# Final_Embedded.net
KiCad netlist of a schematic drawn in Altium Designer
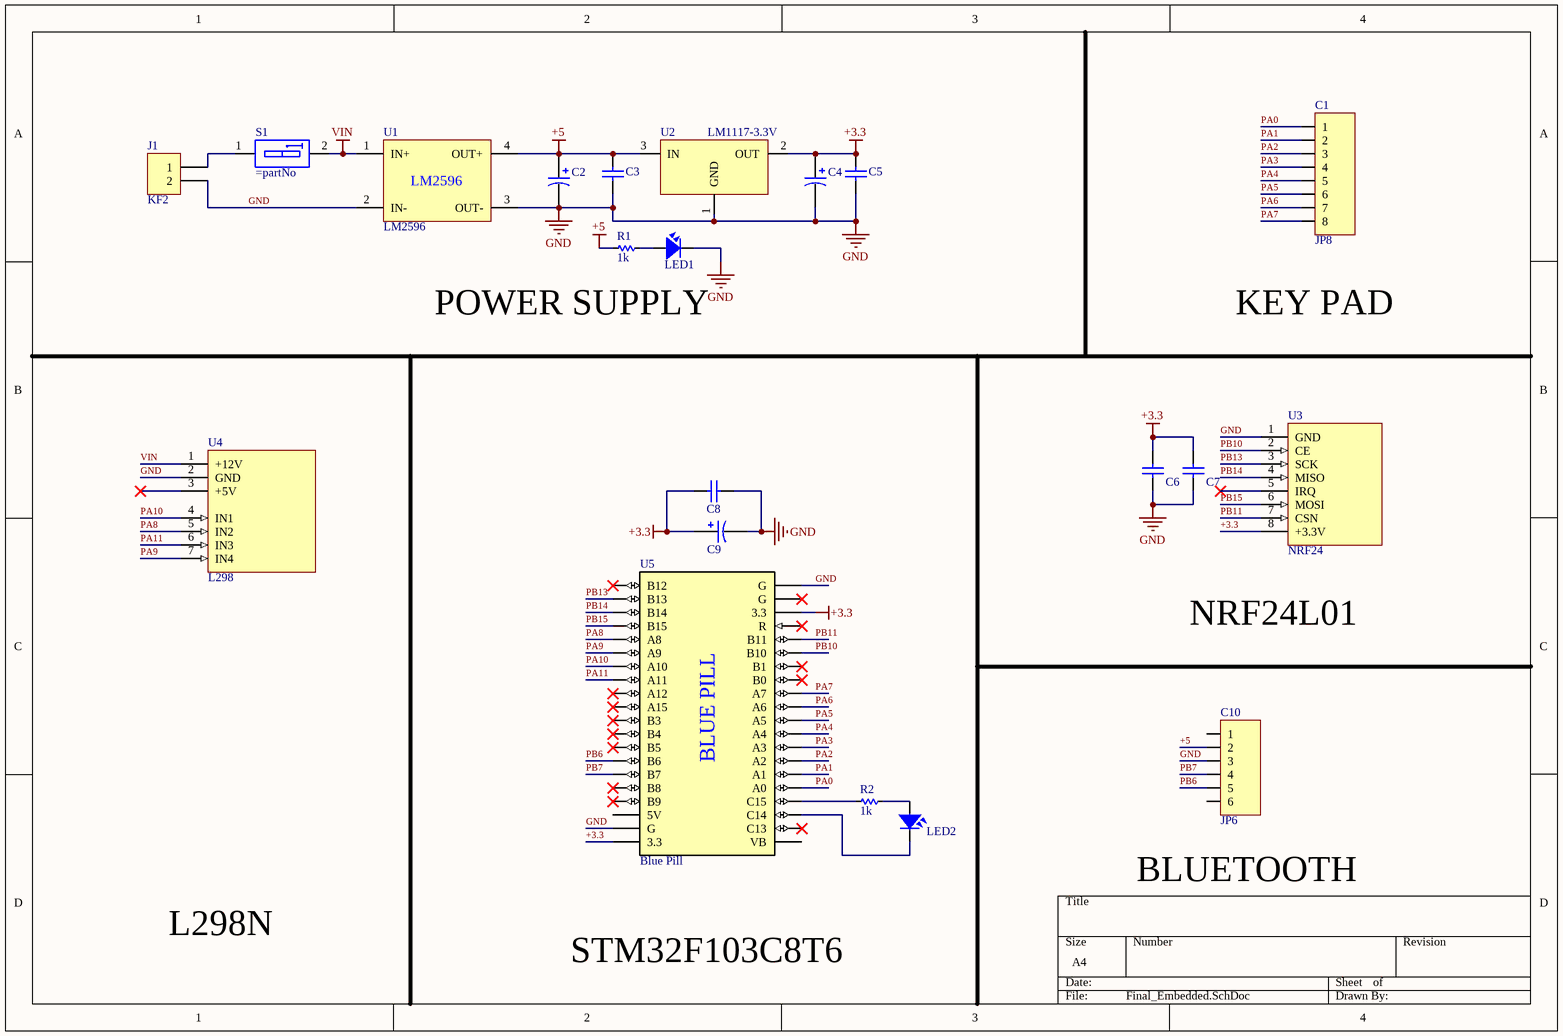
[diagram p0: Final_Embedded.SchDoc]

(export (version "E")
  (design (tool "Eeschema 10.0.6"))
  (components
    (comp (ref "C1")
      (value "JP8")
      (footprint "JP8-D1T")
      (description "WR-PHD 2.54 mm Angled Socket Header")
      (fields
        (field (name "MANUFACTURER") "Würth Elektronik eiSos GmbH")
        (field (name "PARTNO") "613008143121")
        (field (name "CREATED BY") "Karrer Zheng")
      )
      (libsource (lib "TechMT.VN_Lib_Project v2") (part "JP8"))
    )
    (comp (ref "C2")
      (value "47uF")
      (footprint "CAP_ALUM_D080_S35_H115")
      (description "CAP ALUM 47uF 20% 63V RADIAL")
      (fields (field (name "MPN") "CLA4512"))
      (libsource (lib "BYTECH_HW_LIB_2019 (1)") (part "CLA4512"))
    )
    (comp (ref "C3")
      (value "104")
      (footprint "Tu-pico")
      (description "Capacitor")
      (fields (field (name "PUBLISHER") "Altium Limited"))
      (libsource (lib "hphonglib") (part "CapCeramic"))
    )
    (comp (ref "C4")
      (value "47uF")
      (footprint "CAP_ALUM_D080_S35_H115")
      (description "CAP ALUM 47uF 20% 63V RADIAL")
      (fields (field (name "MPN") "CLA4512"))
      (libsource (lib "BYTECH_HW_LIB_2019 (1)") (part "CLA4512"))
    )
    (comp (ref "C5")
      (value "104")
      (footprint "Tu-pico")
      (description "Capacitor")
      (fields (field (name "PUBLISHER") "Altium Limited"))
      (libsource (lib "hphonglib") (part "CapCeramic"))
    )
    (comp (ref "C6")
      (value "104")
      (footprint "Tu-pico")
      (description "Capacitor")
      (fields (field (name "PUBLISHER") "Altium Limited"))
      (libsource (lib "hphonglib") (part "CapCeramic"))
    )
    (comp (ref "C7")
      (value "104")
      (footprint "Tu-pico")
      (description "Capacitor")
      (fields (field (name "PUBLISHER") "Altium Limited"))
      (libsource (lib "hphonglib") (part "CapCeramic"))
    )
    (comp (ref "C8")
      (value "104")
      (footprint "Tu-pico")
      (description "Capacitor")
      (fields (field (name "PUBLISHER") "Altium Limited"))
      (libsource (lib "hphonglib") (part "CapCeramic"))
    )
    (comp (ref "C9")
      (value "47uF")
      (footprint "CAP_ALUM_D080_S35_H115")
      (description "CAP ALUM 47uF 20% 63V RADIAL")
      (fields (field (name "MPN") "CLA4512"))
      (libsource (lib "BYTECH_HW_LIB_2019 (1)") (part "CLA4512"))
    )
    (comp (ref "C10")
      (value "JP6")
      (footprint "JP6-C1T")
      (description "WR-PHD 2.54 mm Angled Socket Header")
      (fields
        (field (name "MANUFACTURER") "Würth Elektronik eiSos GmbH")
        (field (name "PARTNO") "613006143121")
        (field (name "CREATED BY") "Karrer Zheng")
      )
      (libsource (lib "TechMT.VN_Lib_Project v2") (part "JP6"))
    )
    (comp (ref "J1")
      (value "KF2")
      (footprint "KF2-5.08")
      (fields
        (field (name "MANUFACTURER") "Würth Elektronik eiSos GmbH")
        (field (name "PARTNO") "691103110002")
        (field (name "CREATED BY") "Karrer Zheng")
      )
      (libsource (lib "TechMT.VN_Lib_Project v2") (part "KF2"))
    )
    (comp (ref "LED1")
      (value "LED")
      (footprint "LED-3MM-RED")
      (description "LED Single colour Green and Red")
      (libsource (lib "TechMT.VN_Lib_Project v2") (part "LED"))
    )
    (comp (ref "LED2")
      (value "LED")
      (footprint "LED-3MM-GREEN")
      (description "LED Single colour Green and Red")
      (libsource (lib "TechMT.VN_Lib_Project v2") (part "LED"))
    )
    (comp (ref "R1")
      (value "1k")
      (footprint "RES-1/4W-SMALL")
      (description "Res")
      (fields
        (field (name "MANUFACTURER") "Generic Components")
        (field (name "PUBLISHER") "Altium Hobart Technology Centre")
      )
      (libsource (lib "TechMT.VN_Lib_Project v2") (part "Res"))
    )
    (comp (ref "R2")
      (value "1k")
      (footprint "RES-1/8W-SMALL")
      (description "Res")
      (fields
        (field (name "MANUFACTURER") "Generic Components")
        (field (name "PUBLISHER") "Altium Hobart Technology Centre")
      )
      (libsource (lib "TechMT.VN_Lib_Project v2") (part "Res"))
    )
    (comp (ref "S1")
      (value "~")
      (footprint "SW-DIP1")
      (description "WS-DITV 2.54 mm small compact THT flat actuator with top tape")
      (fields
        (field (name "MANUFACTURER") "Wurth Elektronik")
        (field (name "PART NO.") "418127160901")
        (field (name "CREATED BY") "Baojun Chen")
      )
      (libsource (lib "LIBRARY") (part "SWDIP1"))
    )
    (comp (ref "U1")
      (value "LM2596")
      (footprint "AZ_Lib:LM2596 Module")
      (description "DC - DC Buck")
      (libsource (lib "AZ_Lib") (part "LM2596 Module"))
    )
    (comp (ref "U2")
      (value "LM1117-3.3V")
      (footprint "TO220-123")
      (description "800mA Low-Dropout Linear Regulator")
      (fields (field (name "CREATOR") "Nguyen Ba Bien"))
      (libsource (lib "TechMT.VN_Lib_Project v2") (part "LM1117"))
    )
    (comp (ref "U3")
      (value "NRF24")
      (footprint "AZ_Lib:NRF24L01 Module")
      (description "NRF24L01")
      (libsource (lib "AZ_Lib") (part "NRF24L01 Module"))
    )
    (comp (ref "U4")
      (value "L298")
      (footprint "AZ_Lib:L298N Module")
      (description "L298 Module")
      (libsource (lib "AZ_Lib") (part "L298N Module"))
    )
    (comp (ref "U5")
      (value "Blue Pill")
      (footprint "AZ_Lib:Blue Pill STM32F103")
      (description "Blue Pill STM32F103C8T6")
      (libsource (lib "AZ_Lib") (part "Blue Pill STM32F103"))
    )
  )
  (nets
    (net (code "1") (name "+3.3") (class "Default")
      (node (ref "C4") (pin "1") (pinfunction "1_1") (pintype "passive"))
      (node (ref "C5") (pin "2") (pinfunction "2_2") (pintype "passive"))
      (node (ref "C6") (pin "1") (pinfunction "1_1") (pintype "passive"))
      (node (ref "C7") (pin "1") (pinfunction "1_1") (pintype "passive"))
      (node (ref "C8") (pin "1") (pinfunction "1_1") (pintype "passive"))
      (node (ref "C9") (pin "1") (pinfunction "1_1") (pintype "passive"))
      (node (ref "U2") (pin "2") (pinfunction "OUT_2") (pintype "passive"))
      (node (ref "U3") (pin "8") (pinfunction "+3.3V_8") (pintype "power_in"))
      (node (ref "U5") (pin "20") (pinfunction "3.3_20") (pintype "power_in"))
      (node (ref "U5") (pin "38") (pinfunction "3.3_38") (pintype "power_in"))
    )
    (net (code "2") (name "+5") (class "Default")
      (node (ref "C10") (pin "2") (pinfunction "2_2") (pintype "passive"))
      (node (ref "C2") (pin "1") (pinfunction "1_1") (pintype "passive"))
      (node (ref "C3") (pin "2") (pinfunction "2_2") (pintype "passive"))
      (node (ref "R1") (pin "2") (pinfunction "2_2") (pintype "passive"))
      (node (ref "U1") (pin "4") (pinfunction "OUT+_4") (pintype "passive"))
      (node (ref "U2") (pin "3") (pinfunction "IN_3") (pintype "passive"))
    )
    (net (code "3") (name "/PA0") (class "Default")
      (node (ref "C1") (pin "1") (pinfunction "1_1") (pintype "passive"))
      (node (ref "U5") (pin "25") (pinfunction "A0_25") (pintype "bidirectional"))
    )
    (net (code "4") (name "/PA1") (class "Default")
      (node (ref "C1") (pin "2") (pinfunction "2_2") (pintype "passive"))
      (node (ref "U5") (pin "26") (pinfunction "A1_26") (pintype "bidirectional"))
    )
    (net (code "5") (name "/PA2") (class "Default")
      (node (ref "C1") (pin "3") (pinfunction "3_3") (pintype "passive"))
      (node (ref "U5") (pin "27") (pinfunction "A2_27") (pintype "bidirectional"))
    )
    (net (code "6") (name "/PA3") (class "Default")
      (node (ref "C1") (pin "4") (pinfunction "4_4") (pintype "passive"))
      (node (ref "U5") (pin "28") (pinfunction "A3_28") (pintype "bidirectional"))
    )
    (net (code "7") (name "/PA4") (class "Default")
      (node (ref "C1") (pin "5") (pinfunction "5_5") (pintype "passive"))
      (node (ref "U5") (pin "29") (pinfunction "A4_29") (pintype "bidirectional"))
    )
    (net (code "8") (name "/PA5") (class "Default")
      (node (ref "C1") (pin "6") (pinfunction "6_6") (pintype "passive"))
      (node (ref "U5") (pin "30") (pinfunction "A5_30") (pintype "bidirectional"))
    )
    (net (code "9") (name "/PA6") (class "Default")
      (node (ref "C1") (pin "7") (pinfunction "7_7") (pintype "passive"))
      (node (ref "U5") (pin "31") (pinfunction "A6_31") (pintype "bidirectional"))
    )
    (net (code "10") (name "/PA7") (class "Default")
      (node (ref "C1") (pin "8") (pinfunction "8_8") (pintype "passive"))
      (node (ref "U5") (pin "32") (pinfunction "A7_32") (pintype "bidirectional"))
    )
    (net (code "11") (name "/PA8") (class "Default")
      (node (ref "U4") (pin "5") (pinfunction "IN2_5") (pintype "input"))
      (node (ref "U5") (pin "5") (pinfunction "A8_5") (pintype "bidirectional"))
    )
    (net (code "12") (name "/PA9") (class "Default")
      (node (ref "U4") (pin "7") (pinfunction "IN4_7") (pintype "input"))
      (node (ref "U5") (pin "6") (pinfunction "A9_6") (pintype "bidirectional"))
    )
    (net (code "13") (name "/PA10") (class "Default")
      (node (ref "U4") (pin "4") (pinfunction "IN1_4") (pintype "input"))
      (node (ref "U5") (pin "7") (pinfunction "A10_7") (pintype "bidirectional"))
    )
    (net (code "14") (name "/PA11") (class "Default")
      (node (ref "U4") (pin "6") (pinfunction "IN3_6") (pintype "input"))
      (node (ref "U5") (pin "8") (pinfunction "A11_8") (pintype "bidirectional"))
    )
    (net (code "15") (name "/PB6") (class "Default")
      (node (ref "C10") (pin "5") (pinfunction "5_5") (pintype "passive"))
      (node (ref "U5") (pin "14") (pinfunction "B6_14") (pintype "bidirectional"))
    )
    (net (code "16") (name "/PB7") (class "Default")
      (node (ref "C10") (pin "4") (pinfunction "4_4") (pintype "passive"))
      (node (ref "U5") (pin "15") (pinfunction "B7_15") (pintype "bidirectional"))
    )
    (net (code "17") (name "/PB10") (class "Default")
      (node (ref "U3") (pin "2") (pinfunction "CE_2") (pintype "input"))
      (node (ref "U5") (pin "35") (pinfunction "B10_35") (pintype "bidirectional"))
    )
    (net (code "18") (name "/PB11") (class "Default")
      (node (ref "U3") (pin "7") (pinfunction "CSN_7") (pintype "input"))
      (node (ref "U5") (pin "36") (pinfunction "B11_36") (pintype "bidirectional"))
    )
    (net (code "19") (name "/PB13") (class "Default")
      (node (ref "U3") (pin "3") (pinfunction "SCK_3") (pintype "input"))
      (node (ref "U5") (pin "2") (pinfunction "B13_2") (pintype "bidirectional"))
    )
    (net (code "20") (name "/PB14") (class "Default")
      (node (ref "U3") (pin "4") (pinfunction "MISO_4") (pintype "input"))
      (node (ref "U5") (pin "3") (pinfunction "B14_3") (pintype "bidirectional"))
    )
    (net (code "21") (name "/PB15") (class "Default")
      (node (ref "U3") (pin "6") (pinfunction "MOSI_6") (pintype "input"))
      (node (ref "U5") (pin "4") (pinfunction "B15_4") (pintype "bidirectional"))
    )
    (net (code "22") (name "GND") (class "Default")
      (node (ref "C10") (pin "3") (pinfunction "3_3") (pintype "passive"))
      (node (ref "C2") (pin "2") (pinfunction "2_2") (pintype "passive"))
      (node (ref "C3") (pin "1") (pinfunction "1_1") (pintype "passive"))
      (node (ref "C4") (pin "2") (pinfunction "2_2") (pintype "passive"))
      (node (ref "C5") (pin "1") (pinfunction "1_1") (pintype "passive"))
      (node (ref "C6") (pin "2") (pinfunction "2_2") (pintype "passive"))
      (node (ref "C7") (pin "2") (pinfunction "2_2") (pintype "passive"))
      (node (ref "C8") (pin "2") (pinfunction "2_2") (pintype "passive"))
      (node (ref "C9") (pin "2") (pinfunction "2_2") (pintype "passive"))
      (node (ref "J1") (pin "2") (pinfunction "2_2") (pintype "passive"))
      (node (ref "LED1") (pin "2") (pinfunction "2_2") (pintype "passive"))
      (node (ref "U1") (pin "2") (pinfunction "IN-_2") (pintype "passive"))
      (node (ref "U1") (pin "3") (pinfunction "OUT-_3") (pintype "passive"))
      (node (ref "U2") (pin "1") (pinfunction "GND_1") (pintype "passive"))
      (node (ref "U3") (pin "1") (pinfunction "GND_1") (pintype "power_in"))
      (node (ref "U4") (pin "2") (pinfunction "GND_2") (pintype "power_in"))
      (node (ref "U5") (pin "19") (pinfunction "G_19") (pintype "power_in"))
      (node (ref "U5") (pin "40") (pinfunction "G_40") (pintype "power_in"))
    )
    (net (code "23") (name "Net-(J1-Pad1)") (class "Default")
      (node (ref "J1") (pin "1") (pinfunction "1_1") (pintype "passive"))
      (node (ref "S1") (pin "1") (pinfunction "1_1") (pintype "passive"))
    )
    (net (code "24") (name "Net-(LED1-Pad1)") (class "Default")
      (node (ref "LED1") (pin "1") (pinfunction "1_1") (pintype "passive"))
      (node (ref "R1") (pin "1") (pinfunction "1_1") (pintype "passive"))
    )
    (net (code "25") (name "Net-(LED2-Pad1)") (class "Default")
      (node (ref "LED2") (pin "1") (pinfunction "1_1") (pintype "passive"))
      (node (ref "R2") (pin "1") (pinfunction "1_1") (pintype "passive"))
    )
    (net (code "26") (name "Net-(U5-C14)") (class "Default")
      (node (ref "LED2") (pin "2") (pinfunction "2_2") (pintype "passive"))
      (node (ref "U5") (pin "23") (pinfunction "C14_23") (pintype "bidirectional"))
    )
    (net (code "27") (name "Net-(U5-C15)") (class "Default")
      (node (ref "R2") (pin "2") (pinfunction "2_2") (pintype "passive"))
      (node (ref "U5") (pin "24") (pinfunction "C15_24") (pintype "bidirectional"))
    )
    (net (code "28") (name "VIN") (class "Default")
      (node (ref "S1") (pin "2") (pinfunction "2_2") (pintype "passive"))
      (node (ref "U1") (pin "1") (pinfunction "IN+_1") (pintype "passive"))
      (node (ref "U4") (pin "1") (pinfunction "+12V_1") (pintype "power_in"))
    )
    (net (code "29") (name "unconnected-(C10-Pad1)") (class "Default")
      (node (ref "C10") (pin "1") (pinfunction "1_1") (pintype "passive"))
    )
    (net (code "30") (name "unconnected-(C10-Pad6)") (class "Default")
      (node (ref "C10") (pin "6") (pinfunction "6_6") (pintype "passive"))
    )
    (net (code "31") (name "unconnected-(U3-IRQ-Pad5)") (class "Default")
      (node (ref "U3") (pin "5") (pinfunction "IRQ_5") (pintype "passive+no_connect"))
    )
    (net (code "32") (name "unconnected-(U4-+5V-Pad3)") (class "Default")
      (node (ref "U4") (pin "3") (pinfunction "+5V_3") (pintype "power_in+no_connect"))
    )
    (net (code "33") (name "unconnected-(U5-5V-Pad18)") (class "Default")
      (node (ref "U5") (pin "18") (pinfunction "5V_18") (pintype "power_in"))
    )
    (net (code "34") (name "unconnected-(U5-A12-Pad9)") (class "Default")
      (node (ref "U5") (pin "9") (pinfunction "A12_9") (pintype "bidirectional+no_connect"))
    )
    (net (code "35") (name "unconnected-(U5-A15-Pad10)") (class "Default")
      (node (ref "U5") (pin "10") (pinfunction "A15_10") (pintype "bidirectional+no_connect"))
    )
    (net (code "36") (name "unconnected-(U5-B0-Pad33)") (class "Default")
      (node (ref "U5") (pin "33") (pinfunction "B0_33") (pintype "bidirectional+no_connect"))
    )
    (net (code "37") (name "unconnected-(U5-B1-Pad34)") (class "Default")
      (node (ref "U5") (pin "34") (pinfunction "B1_34") (pintype "bidirectional+no_connect"))
    )
    (net (code "38") (name "unconnected-(U5-B3-Pad11)") (class "Default")
      (node (ref "U5") (pin "11") (pinfunction "B3_11") (pintype "bidirectional+no_connect"))
    )
    (net (code "39") (name "unconnected-(U5-B4-Pad12)") (class "Default")
      (node (ref "U5") (pin "12") (pinfunction "B4_12") (pintype "bidirectional+no_connect"))
    )
    (net (code "40") (name "unconnected-(U5-B5-Pad13)") (class "Default")
      (node (ref "U5") (pin "13") (pinfunction "B5_13") (pintype "bidirectional+no_connect"))
    )
    (net (code "41") (name "unconnected-(U5-B8-Pad16)") (class "Default")
      (node (ref "U5") (pin "16") (pinfunction "B8_16") (pintype "bidirectional+no_connect"))
    )
    (net (code "42") (name "unconnected-(U5-B9-Pad17)") (class "Default")
      (node (ref "U5") (pin "17") (pinfunction "B9_17") (pintype "bidirectional+no_connect"))
    )
    (net (code "43") (name "unconnected-(U5-B12-Pad1)") (class "Default")
      (node (ref "U5") (pin "1") (pinfunction "B12_1") (pintype "bidirectional+no_connect"))
    )
    (net (code "44") (name "unconnected-(U5-C13-Pad22)") (class "Default")
      (node (ref "U5") (pin "22") (pinfunction "C13_22") (pintype "bidirectional+no_connect"))
    )
    (net (code "45") (name "unconnected-(U5-G-Pad39)") (class "Default")
      (node (ref "U5") (pin "39") (pinfunction "G_39") (pintype "power_in+no_connect"))
    )
    (net (code "46") (name "unconnected-(U5-R-Pad37)") (class "Default")
      (node (ref "U5") (pin "37") (pinfunction "R_37") (pintype "input+no_connect"))
    )
    (net (code "47") (name "unconnected-(U5-VB-Pad21)") (class "Default")
      (node (ref "U5") (pin "21") (pinfunction "VB_21") (pintype "power_in"))
    )
  )
)
